# dual_motor_driver_v7.net
KiCad netlist of a schematic drawn in EAGLE
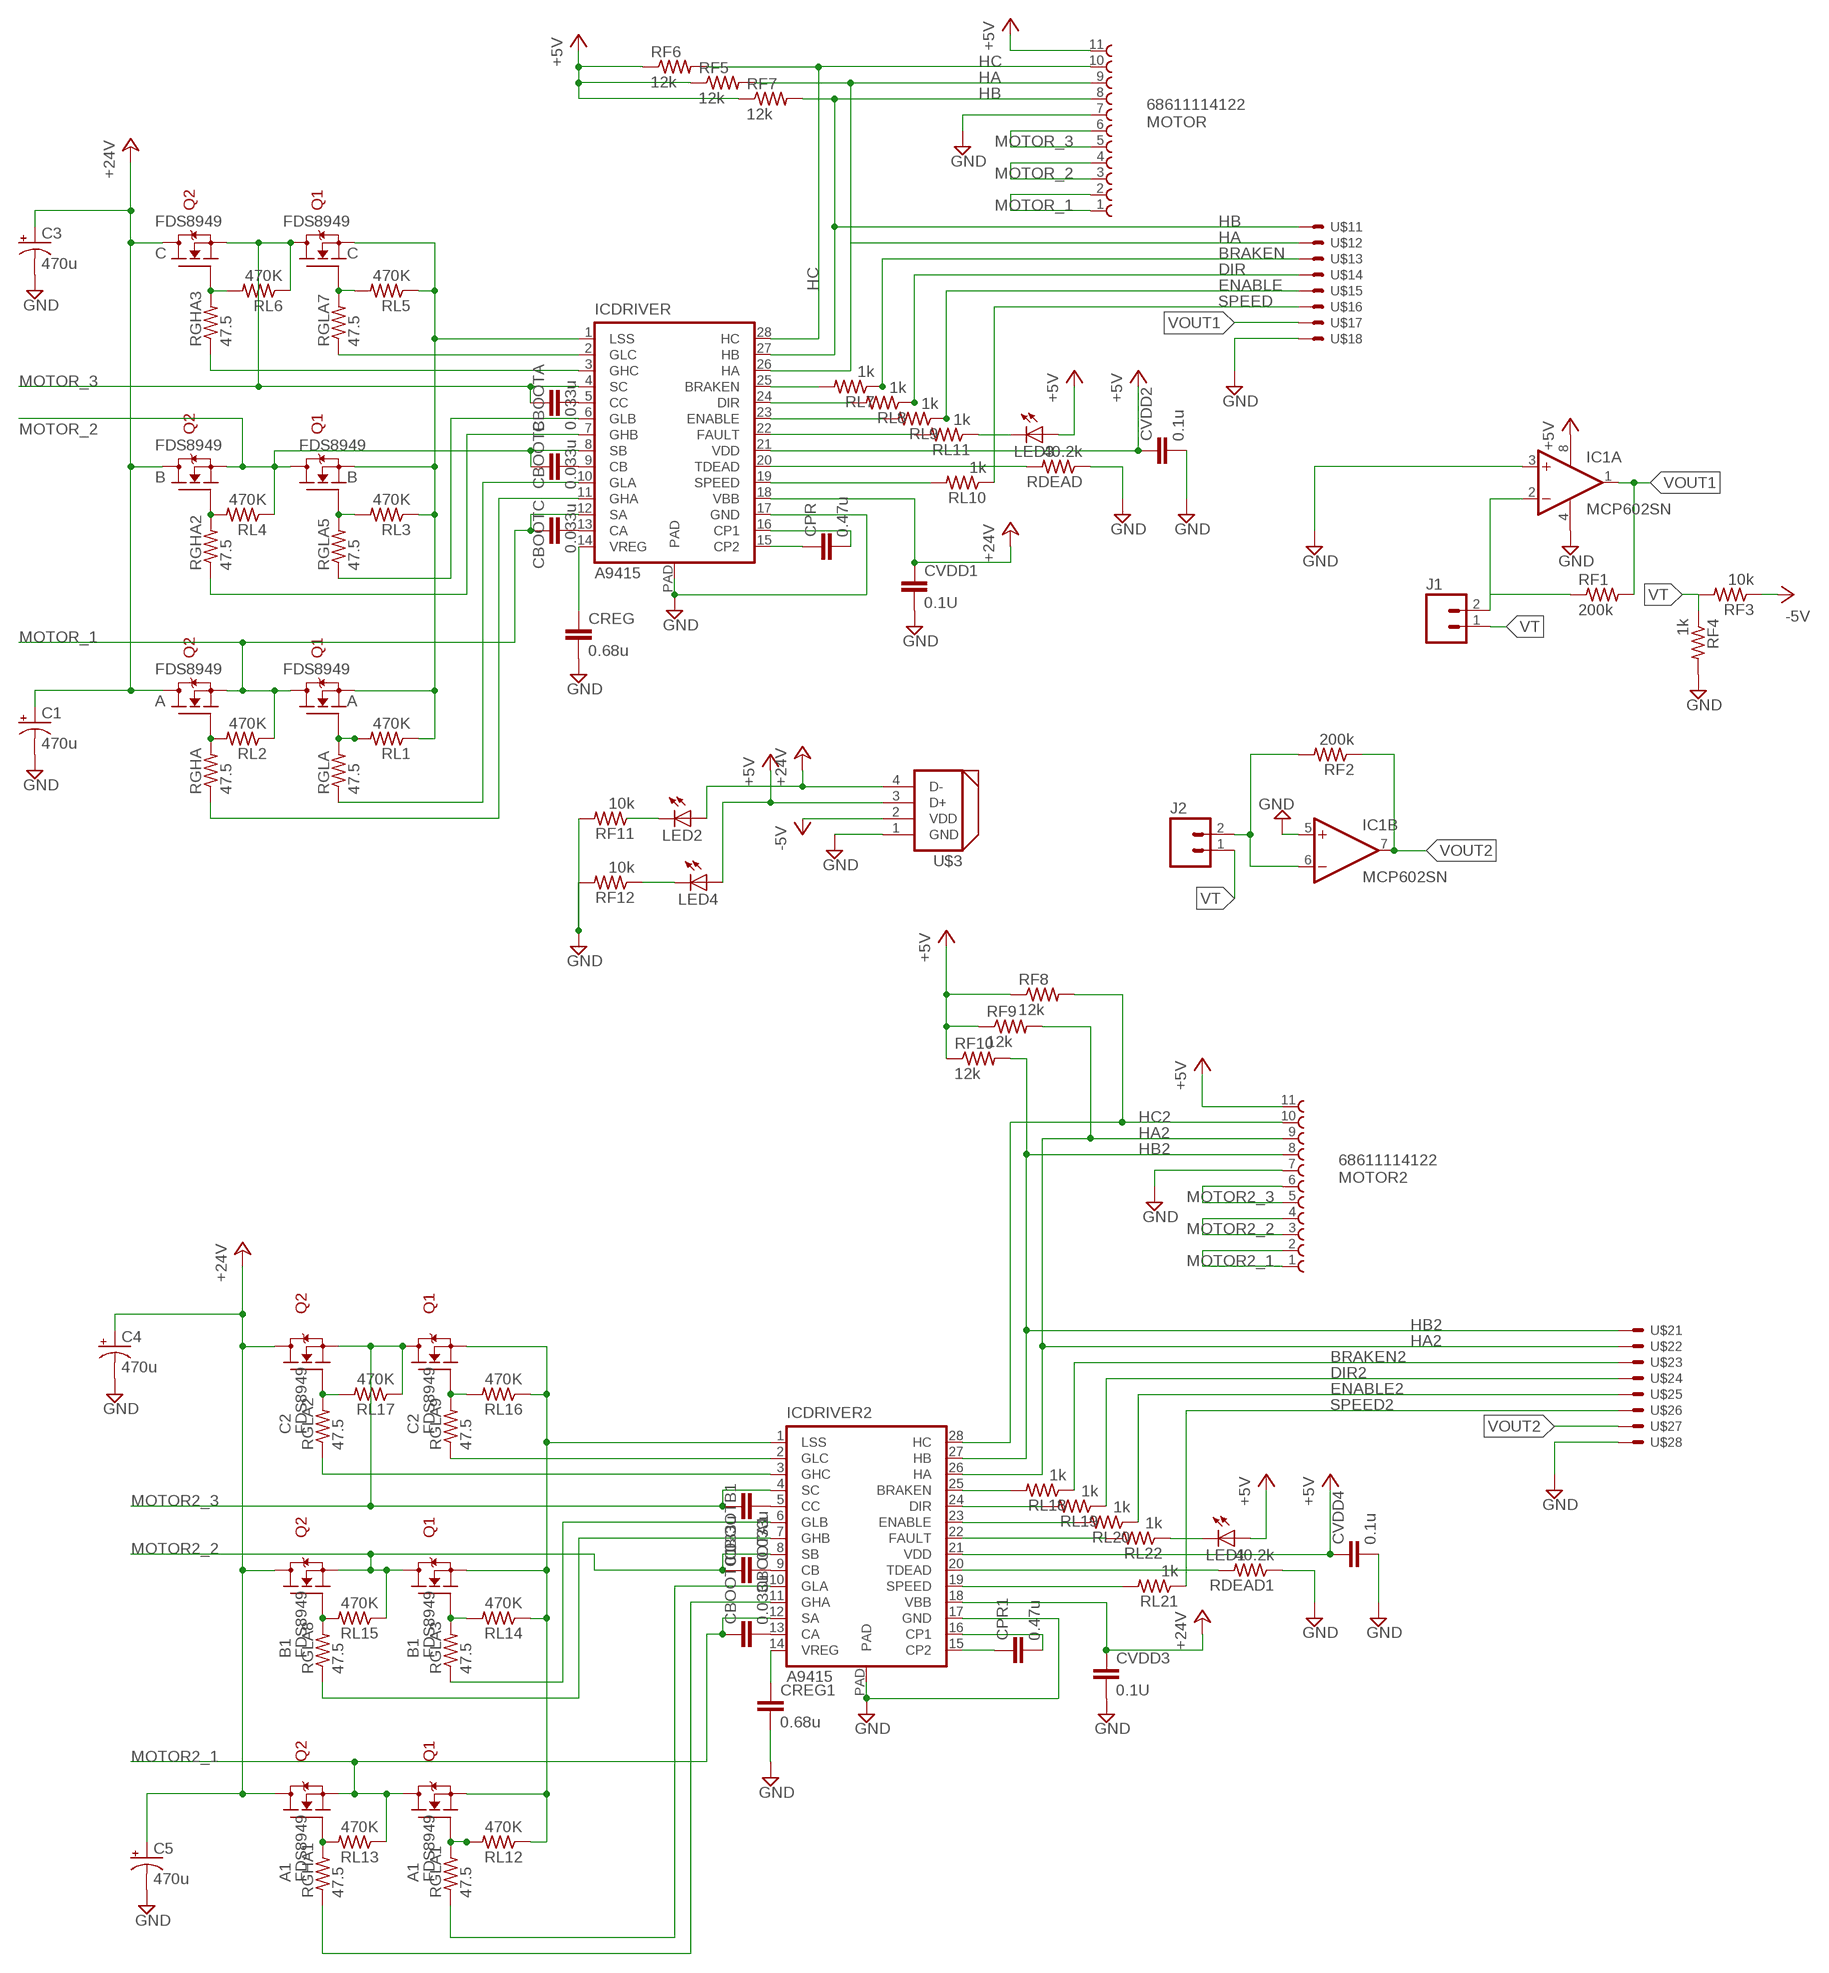
[diagram p0: schematic, sheet 1]

(export (version "E")
  (design (tool "Eeschema 10.0.6"))
  (components
    (comp (ref "A")
      (value "FDS8949")
      (footprint "eagle-import:SOIC8")
      (libsource (lib "eagle-import") (part "FDS8949"))
    )
    (comp (ref "A1")
      (value "FDS8949")
      (footprint "eagle-import:SOIC8")
      (libsource (lib "eagle-import") (part "FDS8949"))
    )
    (comp (ref "B")
      (value "FDS8949")
      (footprint "eagle-import:SOIC8")
      (libsource (lib "eagle-import") (part "FDS8949"))
    )
    (comp (ref "B1")
      (value "FDS8949")
      (footprint "eagle-import:SOIC8")
      (libsource (lib "eagle-import") (part "FDS8949"))
    )
    (comp (ref "C")
      (value "FDS8949")
      (footprint "eagle-import:SOIC8")
      (libsource (lib "eagle-import") (part "FDS8949"))
    )
    (comp (ref "C1")
      (value "470u")
      (footprint "eagle-import:140CLH-1010")
      (libsource (lib "eagle-import") (part "CPOL-US140CLH-1010"))
    )
    (comp (ref "C2")
      (value "FDS8949")
      (footprint "eagle-import:SOIC8")
      (libsource (lib "eagle-import") (part "FDS8949"))
    )
    (comp (ref "C3")
      (value "470u")
      (footprint "eagle-import:140CLH-1010")
      (libsource (lib "eagle-import") (part "CPOL-US140CLH-1010"))
    )
    (comp (ref "C4")
      (value "470u")
      (footprint "eagle-import:140CLH-1010")
      (libsource (lib "eagle-import") (part "CPOL-US140CLH-1010"))
    )
    (comp (ref "C5")
      (value "470u")
      (footprint "eagle-import:140CLH-1010")
      (libsource (lib "eagle-import") (part "CPOL-US140CLH-1010"))
    )
    (comp (ref "CBOOTA")
      (value "0.033u")
      (footprint "eagle-import:C0805")
      (libsource (lib "eagle-import") (part "C-EUC0805"))
    )
    (comp (ref "CBOOTA1")
      (value "0.033u")
      (footprint "eagle-import:C0805")
      (libsource (lib "eagle-import") (part "C-EUC0805"))
    )
    (comp (ref "CBOOTB")
      (value "0.033u")
      (footprint "eagle-import:C0805")
      (libsource (lib "eagle-import") (part "C-EUC0805"))
    )
    (comp (ref "CBOOTB1")
      (value "0.033u")
      (footprint "eagle-import:C0805")
      (libsource (lib "eagle-import") (part "C-EUC0805"))
    )
    (comp (ref "CBOOTC")
      (value "0.033u")
      (footprint "eagle-import:C0805")
      (libsource (lib "eagle-import") (part "C-EUC0805"))
    )
    (comp (ref "CBOOTC1")
      (value "0.033u")
      (footprint "eagle-import:C0805")
      (libsource (lib "eagle-import") (part "C-EUC0805"))
    )
    (comp (ref "CPR")
      (value "0.47u")
      (footprint "eagle-import:C0805")
      (libsource (lib "eagle-import") (part "C-EUC0805"))
    )
    (comp (ref "CPR1")
      (value "0.47u")
      (footprint "eagle-import:C0805")
      (libsource (lib "eagle-import") (part "C-EUC0805"))
    )
    (comp (ref "CREG")
      (value "0.68u")
      (footprint "eagle-import:C0805")
      (libsource (lib "eagle-import") (part "C-EUC0805"))
    )
    (comp (ref "CREG1")
      (value "0.68u")
      (footprint "eagle-import:C0805")
      (libsource (lib "eagle-import") (part "C-EUC0805"))
    )
    (comp (ref "CVDD1")
      (value "0.1U")
      (footprint "eagle-import:C0805")
      (libsource (lib "eagle-import") (part "C-EUC0805"))
    )
    (comp (ref "CVDD2")
      (value "0.1u")
      (footprint "eagle-import:C0805")
      (libsource (lib "eagle-import") (part "C-EUC0805"))
    )
    (comp (ref "CVDD3")
      (value "0.1U")
      (footprint "eagle-import:C0805")
      (libsource (lib "eagle-import") (part "C-EUC0805"))
    )
    (comp (ref "CVDD4")
      (value "0.1u")
      (footprint "eagle-import:C0805")
      (libsource (lib "eagle-import") (part "C-EUC0805"))
    )
    (comp (ref "IC1")
      (value "MCP602SN")
      (footprint "eagle-import:SO08")
      (libsource (lib "eagle-import") (part "MCP602SN"))
    )
    (comp (ref "ICDRIVER")
      (value "A9415")
      (footprint "eagle-import:TSSOP28")
      (libsource (lib "eagle-import") (part "A9415"))
    )
    (comp (ref "ICDRIVER2")
      (value "A9415")
      (footprint "eagle-import:TSSOP28")
      (libsource (lib "eagle-import") (part "A9415"))
    )
    (comp (ref "J1")
      (value "M02PTH")
      (footprint "eagle-import:1X02")
      (libsource (lib "eagle-import") (part "M02PTH"))
    )
    (comp (ref "J2")
      (value "M02PTH")
      (footprint "eagle-import:1X02")
      (libsource (lib "eagle-import") (part "M02PTH"))
    )
    (comp (ref "LED1")
      (value "LEDCHIPLED_0805")
      (footprint "eagle-import:CHIPLED_0805")
      (libsource (lib "eagle-import") (part "LEDCHIPLED_0805"))
    )
    (comp (ref "LED2")
      (value "LEDCHIPLED_0805")
      (footprint "eagle-import:CHIPLED_0805")
      (libsource (lib "eagle-import") (part "LEDCHIPLED_0805"))
    )
    (comp (ref "LED3")
      (value "LEDCHIPLED_0805")
      (footprint "eagle-import:CHIPLED_0805")
      (libsource (lib "eagle-import") (part "LEDCHIPLED_0805"))
    )
    (comp (ref "LED4")
      (value "LEDCHIPLED_0805")
      (footprint "eagle-import:CHIPLED_0805")
      (libsource (lib "eagle-import") (part "LEDCHIPLED_0805"))
    )
    (comp (ref "MOTOR")
      (value "68611114122")
      (footprint "eagle-import:68611114122")
      (libsource (lib "eagle-import") (part "68611114122"))
    )
    (comp (ref "MOTOR2")
      (value "68611114122")
      (footprint "eagle-import:68611114122")
      (libsource (lib "eagle-import") (part "68611114122"))
    )
    (comp (ref "RDEAD")
      (value "40.2k")
      (footprint "eagle-import:R0805")
      (libsource (lib "eagle-import") (part "R-US_R0805"))
    )
    (comp (ref "RDEAD1")
      (value "40.2k")
      (footprint "eagle-import:R0805")
      (libsource (lib "eagle-import") (part "R-US_R0805"))
    )
    (comp (ref "RF1")
      (value "200k")
      (footprint "eagle-import:R0805")
      (libsource (lib "eagle-import") (part "R-US_R0805"))
    )
    (comp (ref "RF2")
      (value "200k")
      (footprint "eagle-import:R0805")
      (libsource (lib "eagle-import") (part "R-US_R0805"))
    )
    (comp (ref "RF3")
      (value "10k")
      (footprint "eagle-import:R0805")
      (libsource (lib "eagle-import") (part "R-US_R0805"))
    )
    (comp (ref "RF4")
      (value "1k")
      (footprint "eagle-import:R0805")
      (libsource (lib "eagle-import") (part "R-US_R0805"))
    )
    (comp (ref "RF5")
      (value "12k")
      (footprint "eagle-import:R0805")
      (libsource (lib "eagle-import") (part "R-US_R0805"))
    )
    (comp (ref "RF6")
      (value "12k")
      (footprint "eagle-import:R0805")
      (libsource (lib "eagle-import") (part "R-US_R0805"))
    )
    (comp (ref "RF7")
      (value "12k")
      (footprint "eagle-import:R0805")
      (libsource (lib "eagle-import") (part "R-US_R0805"))
    )
    (comp (ref "RF8")
      (value "12k")
      (footprint "eagle-import:R0805")
      (libsource (lib "eagle-import") (part "R-US_R0805"))
    )
    (comp (ref "RF9")
      (value "12k")
      (footprint "eagle-import:R0805")
      (libsource (lib "eagle-import") (part "R-US_R0805"))
    )
    (comp (ref "RF10")
      (value "12k")
      (footprint "eagle-import:R0805")
      (libsource (lib "eagle-import") (part "R-US_R0805"))
    )
    (comp (ref "RF11")
      (value "10k")
      (footprint "eagle-import:R0805")
      (libsource (lib "eagle-import") (part "R-US_R0805"))
    )
    (comp (ref "RF12")
      (value "10k")
      (footprint "eagle-import:R0805")
      (libsource (lib "eagle-import") (part "R-US_R0805"))
    )
    (comp (ref "RGHA")
      (value "47.5")
      (footprint "eagle-import:R0805")
      (libsource (lib "eagle-import") (part "R-US_R0805"))
    )
    (comp (ref "RGHA1")
      (value "47.5")
      (footprint "eagle-import:R0805")
      (libsource (lib "eagle-import") (part "R-US_R0805"))
    )
    (comp (ref "RGHA2")
      (value "47.5")
      (footprint "eagle-import:R0805")
      (libsource (lib "eagle-import") (part "R-US_R0805"))
    )
    (comp (ref "RGHA3")
      (value "47.5")
      (footprint "eagle-import:R0805")
      (libsource (lib "eagle-import") (part "R-US_R0805"))
    )
    (comp (ref "RGLA")
      (value "47.5")
      (footprint "eagle-import:R0805")
      (libsource (lib "eagle-import") (part "R-US_R0805"))
    )
    (comp (ref "RGLA1")
      (value "47.5")
      (footprint "eagle-import:R0805")
      (libsource (lib "eagle-import") (part "R-US_R0805"))
    )
    (comp (ref "RGLA2")
      (value "47.5")
      (footprint "eagle-import:R0805")
      (libsource (lib "eagle-import") (part "R-US_R0805"))
    )
    (comp (ref "RGLA3")
      (value "47.5")
      (footprint "eagle-import:R0805")
      (libsource (lib "eagle-import") (part "R-US_R0805"))
    )
    (comp (ref "RGLA5")
      (value "47.5")
      (footprint "eagle-import:R0805")
      (libsource (lib "eagle-import") (part "R-US_R0805"))
    )
    (comp (ref "RGLA7")
      (value "47.5")
      (footprint "eagle-import:R0805")
      (libsource (lib "eagle-import") (part "R-US_R0805"))
    )
    (comp (ref "RGLA8")
      (value "47.5")
      (footprint "eagle-import:R0805")
      (libsource (lib "eagle-import") (part "R-US_R0805"))
    )
    (comp (ref "RGLA9")
      (value "47.5")
      (footprint "eagle-import:R0805")
      (libsource (lib "eagle-import") (part "R-US_R0805"))
    )
    (comp (ref "RL1")
      (value "470K")
      (footprint "eagle-import:R0805")
      (libsource (lib "eagle-import") (part "R-US_R0805"))
    )
    (comp (ref "RL2")
      (value "470K")
      (footprint "eagle-import:R0805")
      (libsource (lib "eagle-import") (part "R-US_R0805"))
    )
    (comp (ref "RL3")
      (value "470K")
      (footprint "eagle-import:R0805")
      (libsource (lib "eagle-import") (part "R-US_R0805"))
    )
    (comp (ref "RL4")
      (value "470K")
      (footprint "eagle-import:R0805")
      (libsource (lib "eagle-import") (part "R-US_R0805"))
    )
    (comp (ref "RL5")
      (value "470K")
      (footprint "eagle-import:R0805")
      (libsource (lib "eagle-import") (part "R-US_R0805"))
    )
    (comp (ref "RL6")
      (value "470K")
      (footprint "eagle-import:R0805")
      (libsource (lib "eagle-import") (part "R-US_R0805"))
    )
    (comp (ref "RL7")
      (value "1k")
      (footprint "eagle-import:R0805")
      (libsource (lib "eagle-import") (part "R-US_R0805"))
    )
    (comp (ref "RL8")
      (value "1k")
      (footprint "eagle-import:R0805")
      (libsource (lib "eagle-import") (part "R-US_R0805"))
    )
    (comp (ref "RL9")
      (value "1k")
      (footprint "eagle-import:R0805")
      (libsource (lib "eagle-import") (part "R-US_R0805"))
    )
    (comp (ref "RL10")
      (value "1k")
      (footprint "eagle-import:R0805")
      (libsource (lib "eagle-import") (part "R-US_R0805"))
    )
    (comp (ref "RL11")
      (value "1k")
      (footprint "eagle-import:R0805")
      (libsource (lib "eagle-import") (part "R-US_R0805"))
    )
    (comp (ref "RL12")
      (value "470K")
      (footprint "eagle-import:R0805")
      (libsource (lib "eagle-import") (part "R-US_R0805"))
    )
    (comp (ref "RL13")
      (value "470K")
      (footprint "eagle-import:R0805")
      (libsource (lib "eagle-import") (part "R-US_R0805"))
    )
    (comp (ref "RL14")
      (value "470K")
      (footprint "eagle-import:R0805")
      (libsource (lib "eagle-import") (part "R-US_R0805"))
    )
    (comp (ref "RL15")
      (value "470K")
      (footprint "eagle-import:R0805")
      (libsource (lib "eagle-import") (part "R-US_R0805"))
    )
    (comp (ref "RL16")
      (value "470K")
      (footprint "eagle-import:R0805")
      (libsource (lib "eagle-import") (part "R-US_R0805"))
    )
    (comp (ref "RL17")
      (value "470K")
      (footprint "eagle-import:R0805")
      (libsource (lib "eagle-import") (part "R-US_R0805"))
    )
    (comp (ref "RL18")
      (value "1k")
      (footprint "eagle-import:R0805")
      (libsource (lib "eagle-import") (part "R-US_R0805"))
    )
    (comp (ref "RL19")
      (value "1k")
      (footprint "eagle-import:R0805")
      (libsource (lib "eagle-import") (part "R-US_R0805"))
    )
    (comp (ref "RL20")
      (value "1k")
      (footprint "eagle-import:R0805")
      (libsource (lib "eagle-import") (part "R-US_R0805"))
    )
    (comp (ref "RL21")
      (value "1k")
      (footprint "eagle-import:R0805")
      (libsource (lib "eagle-import") (part "R-US_R0805"))
    )
    (comp (ref "RL22")
      (value "1k")
      (footprint "eagle-import:R0805")
      (libsource (lib "eagle-import") (part "R-US_R0805"))
    )
    (comp (ref "U$1")
      (value "JST8")
      (footprint "eagle-import:JST")
      (libsource (lib "eagle-import") (part "JST8"))
    )
    (comp (ref "U$2")
      (value "JST8")
      (footprint "eagle-import:JST")
      (libsource (lib "eagle-import") (part "JST8"))
    )
    (comp (ref "U$3")
      (value "DYNAMIXEL_RS485")
      (footprint "eagle-import:DYNAMIXEL_SPOX_04")
      (libsource (lib "eagle-import") (part "DYNAMIXEL_RS485"))
    )
  )
  (nets
    (net (code "1") (name "+5V") (class "Default")
      (node (ref "CVDD2") (pin "1") (pinfunction "1_1") (pintype "passive"))
      (node (ref "CVDD4") (pin "1") (pinfunction "1_1") (pintype "passive"))
      (node (ref "IC1") (pin "8") (pinfunction "V+_8") (pintype "power_in"))
      (node (ref "ICDRIVER") (pin "21") (pinfunction "VDD_21") (pintype "power_in"))
      (node (ref "ICDRIVER2") (pin "21") (pinfunction "VDD_21") (pintype "power_in"))
      (node (ref "LED1") (pin "A") (pinfunction "A_A") (pintype "passive"))
      (node (ref "LED3") (pin "A") (pinfunction "A_A") (pintype "passive"))
      (node (ref "LED4") (pin "A") (pinfunction "A_A") (pintype "passive"))
      (node (ref "MOTOR") (pin "11") (pinfunction "11_11") (pintype "passive"))
      (node (ref "MOTOR2") (pin "11") (pinfunction "11_11") (pintype "passive"))
      (node (ref "RF10") (pin "1") (pinfunction "1_1") (pintype "passive"))
      (node (ref "RF5") (pin "1") (pinfunction "1_1") (pintype "passive"))
      (node (ref "RF6") (pin "1") (pinfunction "1_1") (pintype "passive"))
      (node (ref "RF7") (pin "1") (pinfunction "1_1") (pintype "passive"))
      (node (ref "RF8") (pin "1") (pinfunction "1_1") (pintype "passive"))
      (node (ref "RF9") (pin "1") (pinfunction "1_1") (pintype "passive"))
      (node (ref "U$3") (pin "3") (pinfunction "D+_3") (pintype "bidirectional"))
    )
    (net (code "2") (name "+24V") (class "Default")
      (node (ref "A") (pin "5") (pinfunction "D2_5") (pintype "passive"))
      (node (ref "A") (pin "6") (pinfunction "D2_6") (pintype "passive"))
      (node (ref "A1") (pin "5") (pinfunction "D2_5") (pintype "passive"))
      (node (ref "A1") (pin "6") (pinfunction "D2_6") (pintype "passive"))
      (node (ref "B") (pin "5") (pinfunction "D2_5") (pintype "passive"))
      (node (ref "B") (pin "6") (pinfunction "D2_6") (pintype "passive"))
      (node (ref "B1") (pin "5") (pinfunction "D2_5") (pintype "passive"))
      (node (ref "B1") (pin "6") (pinfunction "D2_6") (pintype "passive"))
      (node (ref "C") (pin "5") (pinfunction "D2_5") (pintype "passive"))
      (node (ref "C") (pin "6") (pinfunction "D2_6") (pintype "passive"))
      (node (ref "C1") (pin "+") (pinfunction "+_+") (pintype "passive"))
      (node (ref "C2") (pin "5") (pinfunction "D2_5") (pintype "passive"))
      (node (ref "C2") (pin "6") (pinfunction "D2_6") (pintype "passive"))
      (node (ref "C3") (pin "+") (pinfunction "+_+") (pintype "passive"))
      (node (ref "C4") (pin "+") (pinfunction "+_+") (pintype "passive"))
      (node (ref "C5") (pin "+") (pinfunction "+_+") (pintype "passive"))
      (node (ref "CVDD1") (pin "1") (pinfunction "1_1") (pintype "passive"))
      (node (ref "CVDD3") (pin "1") (pinfunction "1_1") (pintype "passive"))
      (node (ref "ICDRIVER") (pin "18") (pinfunction "VBB_18") (pintype "power_in"))
      (node (ref "ICDRIVER2") (pin "18") (pinfunction "VBB_18") (pintype "power_in"))
      (node (ref "LED2") (pin "A") (pinfunction "A_A") (pintype "passive"))
      (node (ref "U$3") (pin "4") (pinfunction "D-_4") (pintype "bidirectional"))
    )
    (net (code "3") (name "-5V") (class "Default")
      (node (ref "RF3") (pin "1") (pinfunction "1_1") (pintype "passive"))
      (node (ref "U$3") (pin "2") (pinfunction "VDD_2") (pintype "power_in"))
    )
    (net (code "4") (name "/BRAKEN") (class "Default")
      (node (ref "RL7") (pin "1") (pinfunction "1_1") (pintype "passive"))
      (node (ref "U$1") (pin "3") (pinfunction "S_3") (pintype "passive"))
    )
    (net (code "5") (name "/BRAKEN2") (class "Default")
      (node (ref "RL18") (pin "1") (pinfunction "1_1") (pintype "passive"))
      (node (ref "U$2") (pin "3") (pinfunction "S_3") (pintype "passive"))
    )
    (net (code "6") (name "/DIR") (class "Default")
      (node (ref "RL8") (pin "1") (pinfunction "1_1") (pintype "passive"))
      (node (ref "U$1") (pin "4") (pinfunction "S_4") (pintype "passive"))
    )
    (net (code "7") (name "/DIR2") (class "Default")
      (node (ref "RL19") (pin "1") (pinfunction "1_1") (pintype "passive"))
      (node (ref "U$2") (pin "4") (pinfunction "S_4") (pintype "passive"))
    )
    (net (code "8") (name "/ENABLE") (class "Default")
      (node (ref "RL9") (pin "1") (pinfunction "1_1") (pintype "passive"))
      (node (ref "U$1") (pin "5") (pinfunction "S_5") (pintype "passive"))
    )
    (net (code "9") (name "/ENABLE2") (class "Default")
      (node (ref "RL20") (pin "1") (pinfunction "1_1") (pintype "passive"))
      (node (ref "U$2") (pin "5") (pinfunction "S_5") (pintype "passive"))
    )
    (net (code "10") (name "/HA") (class "Default")
      (node (ref "ICDRIVER") (pin "26") (pinfunction "HA_26") (pintype "input"))
      (node (ref "MOTOR") (pin "9") (pinfunction "9_9") (pintype "passive"))
      (node (ref "RF5") (pin "2") (pinfunction "2_2") (pintype "passive"))
      (node (ref "U$1") (pin "2") (pinfunction "S_2") (pintype "passive"))
    )
    (net (code "11") (name "/HA2") (class "Default")
      (node (ref "ICDRIVER2") (pin "26") (pinfunction "HA_26") (pintype "input"))
      (node (ref "MOTOR2") (pin "9") (pinfunction "9_9") (pintype "passive"))
      (node (ref "RF9") (pin "2") (pinfunction "2_2") (pintype "passive"))
      (node (ref "U$2") (pin "2") (pinfunction "S_2") (pintype "passive"))
    )
    (net (code "12") (name "/HB") (class "Default")
      (node (ref "ICDRIVER") (pin "27") (pinfunction "HB_27") (pintype "input"))
      (node (ref "MOTOR") (pin "8") (pinfunction "8_8") (pintype "passive"))
      (node (ref "RF7") (pin "2") (pinfunction "2_2") (pintype "passive"))
      (node (ref "U$1") (pin "1") (pinfunction "S_1") (pintype "passive"))
    )
    (net (code "13") (name "/HB2") (class "Default")
      (node (ref "ICDRIVER2") (pin "27") (pinfunction "HB_27") (pintype "input"))
      (node (ref "MOTOR2") (pin "8") (pinfunction "8_8") (pintype "passive"))
      (node (ref "RF10") (pin "2") (pinfunction "2_2") (pintype "passive"))
      (node (ref "U$2") (pin "1") (pinfunction "S_1") (pintype "passive"))
    )
    (net (code "14") (name "/HC") (class "Default")
      (node (ref "ICDRIVER") (pin "28") (pinfunction "HC_28") (pintype "input"))
      (node (ref "MOTOR") (pin "10") (pinfunction "10_10") (pintype "passive"))
      (node (ref "RF6") (pin "2") (pinfunction "2_2") (pintype "passive"))
    )
    (net (code "15") (name "/HC2") (class "Default")
      (node (ref "ICDRIVER2") (pin "28") (pinfunction "HC_28") (pintype "input"))
      (node (ref "MOTOR2") (pin "10") (pinfunction "10_10") (pintype "passive"))
      (node (ref "RF8") (pin "2") (pinfunction "2_2") (pintype "passive"))
    )
    (net (code "16") (name "/MOTOR2_1") (class "Default")
      (node (ref "A1") (pin "3") (pinfunction "S2_3") (pintype "passive"))
      (node (ref "A1") (pin "7") (pinfunction "D1_7") (pintype "passive"))
      (node (ref "A1") (pin "8") (pinfunction "D1_8") (pintype "passive"))
      (node (ref "CBOOTC1") (pin "1") (pinfunction "1_1") (pintype "passive"))
      (node (ref "ICDRIVER2") (pin "12") (pinfunction "SA_12") (pintype "output"))
      (node (ref "MOTOR2") (pin "1") (pinfunction "1_1") (pintype "passive"))
      (node (ref "MOTOR2") (pin "2") (pinfunction "2_2") (pintype "passive"))
      (node (ref "RL13") (pin "1") (pinfunction "1_1") (pintype "passive"))
    )
    (net (code "17") (name "/MOTOR2_2") (class "Default")
      (node (ref "B1") (pin "3") (pinfunction "S2_3") (pintype "passive"))
      (node (ref "B1") (pin "7") (pinfunction "D1_7") (pintype "passive"))
      (node (ref "B1") (pin "8") (pinfunction "D1_8") (pintype "passive"))
      (node (ref "CBOOTB1") (pin "1") (pinfunction "1_1") (pintype "passive"))
      (node (ref "ICDRIVER2") (pin "8") (pinfunction "SB_8") (pintype "output"))
      (node (ref "MOTOR2") (pin "3") (pinfunction "3_3") (pintype "passive"))
      (node (ref "MOTOR2") (pin "4") (pinfunction "4_4") (pintype "passive"))
      (node (ref "RL15") (pin "1") (pinfunction "1_1") (pintype "passive"))
    )
    (net (code "18") (name "/MOTOR2_3") (class "Default")
      (node (ref "C2") (pin "3") (pinfunction "S2_3") (pintype "passive"))
      (node (ref "C2") (pin "7") (pinfunction "D1_7") (pintype "passive"))
      (node (ref "C2") (pin "8") (pinfunction "D1_8") (pintype "passive"))
      (node (ref "CBOOTA1") (pin "2") (pinfunction "2_2") (pintype "passive"))
      (node (ref "ICDRIVER2") (pin "4") (pinfunction "SC_4") (pintype "output"))
      (node (ref "MOTOR2") (pin "5") (pinfunction "5_5") (pintype "passive"))
      (node (ref "MOTOR2") (pin "6") (pinfunction "6_6") (pintype "passive"))
      (node (ref "RL17") (pin "1") (pinfunction "1_1") (pintype "passive"))
    )
    (net (code "19") (name "/MOTOR_1") (class "Default")
      (node (ref "A") (pin "3") (pinfunction "S2_3") (pintype "passive"))
      (node (ref "A") (pin "7") (pinfunction "D1_7") (pintype "passive"))
      (node (ref "A") (pin "8") (pinfunction "D1_8") (pintype "passive"))
      (node (ref "CBOOTC") (pin "1") (pinfunction "1_1") (pintype "passive"))
      (node (ref "ICDRIVER") (pin "12") (pinfunction "SA_12") (pintype "output"))
      (node (ref "MOTOR") (pin "1") (pinfunction "1_1") (pintype "passive"))
      (node (ref "MOTOR") (pin "2") (pinfunction "2_2") (pintype "passive"))
      (node (ref "RL2") (pin "1") (pinfunction "1_1") (pintype "passive"))
    )
    (net (code "20") (name "/MOTOR_2") (class "Default")
      (node (ref "B") (pin "3") (pinfunction "S2_3") (pintype "passive"))
      (node (ref "B") (pin "7") (pinfunction "D1_7") (pintype "passive"))
      (node (ref "B") (pin "8") (pinfunction "D1_8") (pintype "passive"))
      (node (ref "CBOOTB") (pin "1") (pinfunction "1_1") (pintype "passive"))
      (node (ref "ICDRIVER") (pin "8") (pinfunction "SB_8") (pintype "output"))
      (node (ref "MOTOR") (pin "3") (pinfunction "3_3") (pintype "passive"))
      (node (ref "MOTOR") (pin "4") (pinfunction "4_4") (pintype "passive"))
      (node (ref "RL4") (pin "1") (pinfunction "1_1") (pintype "passive"))
    )
    (net (code "21") (name "/MOTOR_3") (class "Default")
      (node (ref "C") (pin "3") (pinfunction "S2_3") (pintype "passive"))
      (node (ref "C") (pin "7") (pinfunction "D1_7") (pintype "passive"))
      (node (ref "C") (pin "8") (pinfunction "D1_8") (pintype "passive"))
      (node (ref "CBOOTA") (pin "2") (pinfunction "2_2") (pintype "passive"))
      (node (ref "ICDRIVER") (pin "4") (pinfunction "SC_4") (pintype "output"))
      (node (ref "MOTOR") (pin "5") (pinfunction "5_5") (pintype "passive"))
      (node (ref "MOTOR") (pin "6") (pinfunction "6_6") (pintype "passive"))
      (node (ref "RL6") (pin "1") (pinfunction "1_1") (pintype "passive"))
    )
    (net (code "22") (name "/SPEED") (class "Default")
      (node (ref "RL10") (pin "1") (pinfunction "1_1") (pintype "passive"))
      (node (ref "U$1") (pin "6") (pinfunction "S_6") (pintype "passive"))
    )
    (net (code "23") (name "/SPEED2") (class "Default")
      (node (ref "RL21") (pin "1") (pinfunction "1_1") (pintype "passive"))
      (node (ref "U$2") (pin "6") (pinfunction "S_6") (pintype "passive"))
    )
    (net (code "24") (name "GND") (class "Default")
      (node (ref "A") (pin "1") (pinfunction "S1_1") (pintype "passive"))
      (node (ref "A1") (pin "1") (pinfunction "S1_1") (pintype "passive"))
      (node (ref "B") (pin "1") (pinfunction "S1_1") (pintype "passive"))
      (node (ref "B1") (pin "1") (pinfunction "S1_1") (pintype "passive"))
      (node (ref "C") (pin "1") (pinfunction "S1_1") (pintype "passive"))
      (node (ref "C1") (pin "-") (pinfunction "-_-") (pintype "passive"))
      (node (ref "C2") (pin "1") (pinfunction "S1_1") (pintype "passive"))
      (node (ref "C3") (pin "-") (pinfunction "-_-") (pintype "passive"))
      (node (ref "C4") (pin "-") (pinfunction "-_-") (pintype "passive"))
      (node (ref "C5") (pin "-") (pinfunction "-_-") (pintype "passive"))
      (node (ref "CREG") (pin "2") (pinfunction "2_2") (pintype "passive"))
      (node (ref "CREG1") (pin "2") (pinfunction "2_2") (pintype "passive"))
      (node (ref "CVDD1") (pin "2") (pinfunction "2_2") (pintype "passive"))
      (node (ref "CVDD2") (pin "2") (pinfunction "2_2") (pintype "passive"))
      (node (ref "CVDD3") (pin "2") (pinfunction "2_2") (pintype "passive"))
      (node (ref "CVDD4") (pin "2") (pinfunction "2_2") (pintype "passive"))
      (node (ref "IC1") (pin "3") (pinfunction "+IN_3") (pintype "input"))
      (node (ref "IC1") (pin "4") (pinfunction "V-_4") (pintype "power_in"))
      (node (ref "IC1") (pin "5") (pinfunction "+IN_5") (pintype "input"))
      (node (ref "ICDRIVER") (pin "1") (pinfunction "LSS_1") (pintype "input"))
      (node (ref "ICDRIVER") (pin "17") (pinfunction "GND_17") (pintype "power_in"))
      (node (ref "ICDRIVER") (pin "PAD") (pinfunction "PAD_PAD") (pintype "power_in"))
      (node (ref "ICDRIVER2") (pin "1") (pinfunction "LSS_1") (pintype "input"))
      (node (ref "ICDRIVER2") (pin "17") (pinfunction "GND_17") (pintype "power_in"))
      (node (ref "ICDRIVER2") (pin "PAD") (pinfunction "PAD_PAD") (pintype "power_in"))
      (node (ref "MOTOR") (pin "7") (pinfunction "7_7") (pintype "passive"))
      (node (ref "MOTOR2") (pin "7") (pinfunction "7_7") (pintype "passive"))
      (node (ref "RDEAD") (pin "1") (pinfunction "1_1") (pintype "passive"))
      (node (ref "RDEAD1") (pin "1") (pinfunction "1_1") (pintype "passive"))
      (node (ref "RF11") (pin "2") (pinfunction "2_2") (pintype "passive"))
      (node (ref "RF12") (pin "2") (pinfunction "2_2") (pintype "passive"))
      (node (ref "RF4") (pin "2") (pinfunction "2_2") (pintype "passive"))
      (node (ref "RL1") (pin "1") (pinfunction "1_1") (pintype "passive"))
      (node (ref "RL12") (pin "1") (pinfunction "1_1") (pintype "passive"))
      (node (ref "RL14") (pin "1") (pinfunction "1_1") (pintype "passive"))
      (node (ref "RL16") (pin "1") (pinfunction "1_1") (pintype "passive"))
      (node (ref "RL3") (pin "1") (pinfunction "1_1") (pintype "passive"))
      (node (ref "RL5") (pin "1") (pinfunction "1_1") (pintype "passive"))
      (node (ref "U$1") (pin "8") (pinfunction "S_8") (pintype "passive"))
      (node (ref "U$2") (pin "8") (pinfunction "S_8") (pintype "passive"))
      (node (ref "U$3") (pin "1") (pinfunction "GND_1") (pintype "power_in"))
    )
    (net (code "25") (name "Net-(A-G1)") (class "Default")
      (node (ref "A") (pin "2") (pinfunction "G1_2") (pintype "passive"))
      (node (ref "RGLA") (pin "2") (pinfunction "2_2") (pintype "passive"))
      (node (ref "RL1") (pin "2") (pinfunction "2_2") (pintype "passive"))
    )
    (net (code "26") (name "Net-(A-G2)") (class "Default")
      (node (ref "A") (pin "4") (pinfunction "G2_4") (pintype "passive"))
      (node (ref "RGHA") (pin "2") (pinfunction "2_2") (pintype "passive"))
      (node (ref "RL2") (pin "2") (pinfunction "2_2") (pintype "passive"))
    )
    (net (code "27") (name "Net-(A1-G1)") (class "Default")
      (node (ref "A1") (pin "2") (pinfunction "G1_2") (pintype "passive"))
      (node (ref "RGLA1") (pin "2") (pinfunction "2_2") (pintype "passive"))
      (node (ref "RL12") (pin "2") (pinfunction "2_2") (pintype "passive"))
    )
    (net (code "28") (name "Net-(A1-G2)") (class "Default")
      (node (ref "A1") (pin "4") (pinfunction "G2_4") (pintype "passive"))
      (node (ref "RGHA1") (pin "2") (pinfunction "2_2") (pintype "passive"))
      (node (ref "RL13") (pin "2") (pinfunction "2_2") (pintype "passive"))
    )
    (net (code "29") (name "Net-(B-G1)") (class "Default")
      (node (ref "B") (pin "2") (pinfunction "G1_2") (pintype "passive"))
      (node (ref "RGLA5") (pin "2") (pinfunction "2_2") (pintype "passive"))
      (node (ref "RL3") (pin "2") (pinfunction "2_2") (pintype "passive"))
    )
    (net (code "30") (name "Net-(B-G2)") (class "Default")
      (node (ref "B") (pin "4") (pinfunction "G2_4") (pintype "passive"))
      (node (ref "RGHA2") (pin "2") (pinfunction "2_2") (pintype "passive"))
      (node (ref "RL4") (pin "2") (pinfunction "2_2") (pintype "passive"))
    )
    (net (code "31") (name "Net-(B1-G1)") (class "Default")
      (node (ref "B1") (pin "2") (pinfunction "G1_2") (pintype "passive"))
      (node (ref "RGLA3") (pin "2") (pinfunction "2_2") (pintype "passive"))
      (node (ref "RL14") (pin "2") (pinfunction "2_2") (pintype "passive"))
    )
    (net (code "32") (name "Net-(B1-G2)") (class "Default")
      (node (ref "B1") (pin "4") (pinfunction "G2_4") (pintype "passive"))
      (node (ref "RGLA8") (pin "2") (pinfunction "2_2") (pintype "passive"))
      (node (ref "RL15") (pin "2") (pinfunction "2_2") (pintype "passive"))
    )
    (net (code "33") (name "Net-(C-G1)") (class "Default")
      (node (ref "C") (pin "2") (pinfunction "G1_2") (pintype "passive"))
      (node (ref "RGLA7") (pin "2") (pinfunction "2_2") (pintype "passive"))
      (node (ref "RL5") (pin "2") (pinfunction "2_2") (pintype "passive"))
    )
    (net (code "34") (name "Net-(C-G2)") (class "Default")
      (node (ref "C") (pin "4") (pinfunction "G2_4") (pintype "passive"))
      (node (ref "RGHA3") (pin "2") (pinfunction "2_2") (pintype "passive"))
      (node (ref "RL6") (pin "2") (pinfunction "2_2") (pintype "passive"))
    )
    (net (code "35") (name "Net-(C2-G1)") (class "Default")
      (node (ref "C2") (pin "2") (pinfunction "G1_2") (pintype "passive"))
      (node (ref "RGLA9") (pin "2") (pinfunction "2_2") (pintype "passive"))
      (node (ref "RL16") (pin "2") (pinfunction "2_2") (pintype "passive"))
    )
    (net (code "36") (name "Net-(C2-G2)") (class "Default")
      (node (ref "C2") (pin "4") (pinfunction "G2_4") (pintype "passive"))
      (node (ref "RGLA2") (pin "2") (pinfunction "2_2") (pintype "passive"))
      (node (ref "RL17") (pin "2") (pinfunction "2_2") (pintype "passive"))
    )
    (net (code "37") (name "Net-(IC1A--IN)") (class "Default")
      (node (ref "IC1") (pin "2") (pinfunction "-IN_2") (pintype "input"))
      (node (ref "J1") (pin "2") (pinfunction "2_2") (pintype "passive"))
      (node (ref "RF1") (pin "1") (pinfunction "1_1") (pintype "passive"))
    )
    (net (code "38") (name "Net-(IC1B--IN)") (class "Default")
      (node (ref "IC1") (pin "6") (pinfunction "-IN_6") (pintype "input"))
      (node (ref "J2") (pin "2") (pinfunction "2_2") (pintype "passive"))
      (node (ref "RF2") (pin "2") (pinfunction "2_2") (pintype "passive"))
    )
    (net (code "39") (name "Net-(ICDRIVER-BRAKEN)") (class "Default")
      (node (ref "ICDRIVER") (pin "25") (pinfunction "BRAKEN_25") (pintype "bidirectional"))
      (node (ref "RL7") (pin "2") (pinfunction "2_2") (pintype "passive"))
    )
    (net (code "40") (name "Net-(ICDRIVER-CA)") (class "Default")
      (node (ref "CBOOTC") (pin "2") (pinfunction "2_2") (pintype "passive"))
      (node (ref "ICDRIVER") (pin "13") (pinfunction "CA_13") (pintype "output"))
    )
    (net (code "41") (name "Net-(ICDRIVER-CB)") (class "Default")
      (node (ref "CBOOTB") (pin "2") (pinfunction "2_2") (pintype "passive"))
      (node (ref "ICDRIVER") (pin "9") (pinfunction "CB_9") (pintype "output"))
    )
    (net (code "42") (name "Net-(ICDRIVER-CC)") (class "Default")
      (node (ref "CBOOTA") (pin "1") (pinfunction "1_1") (pintype "passive"))
      (node (ref "ICDRIVER") (pin "5") (pinfunction "CC_5") (pintype "output"))
    )
    (net (code "43") (name "Net-(ICDRIVER-CP1)") (class "Default")
      (node (ref "CPR") (pin "2") (pinfunction "2_2") (pintype "passive"))
      (node (ref "ICDRIVER") (pin "16") (pinfunction "CP1_16") (pintype "input"))
    )
    (net (code "44") (name "Net-(ICDRIVER-CP2)") (class "Default")
      (node (ref "CPR") (pin "1") (pinfunction "1_1") (pintype "passive"))
      (node (ref "ICDRIVER") (pin "15") (pinfunction "CP2_15") (pintype "passive"))
    )
    (net (code "45") (name "Net-(ICDRIVER-DIR)") (class "Default")
      (node (ref "ICDRIVER") (pin "24") (pinfunction "DIR_24") (pintype "input"))
      (node (ref "RL8") (pin "2") (pinfunction "2_2") (pintype "passive"))
    )
    (net (code "46") (name "Net-(ICDRIVER-ENABLE)") (class "Default")
      (node (ref "ICDRIVER") (pin "23") (pinfunction "ENABLE_23") (pintype "input"))
      (node (ref "RL9") (pin "2") (pinfunction "2_2") (pintype "passive"))
    )
    (net (code "47") (name "Net-(ICDRIVER-FAULT)") (class "Default")
      (node (ref "ICDRIVER") (pin "22") (pinfunction "FAULT_22") (pintype "output"))
      (node (ref "RL11") (pin "2") (pinfunction "2_2") (pintype "passive"))
    )
    (net (code "48") (name "Net-(ICDRIVER-GHA)") (class "Default")
      (node (ref "ICDRIVER") (pin "11") (pinfunction "GHA_11") (pintype "output"))
      (node (ref "RGHA") (pin "1") (pinfunction "1_1") (pintype "passive"))
    )
    (net (code "49") (name "Net-(ICDRIVER-GHB)") (class "Default")
      (node (ref "ICDRIVER") (pin "7") (pinfunction "GHB_7") (pintype "output"))
      (node (ref "RGHA2") (pin "1") (pinfunction "1_1") (pintype "passive"))
    )
    (net (code "50") (name "Net-(ICDRIVER-GHC)") (class "Default")
      (node (ref "ICDRIVER") (pin "3") (pinfunction "GHC_3") (pintype "output"))
      (node (ref "RGHA3") (pin "1") (pinfunction "1_1") (pintype "passive"))
    )
    (net (code "51") (name "Net-(ICDRIVER-GLA)") (class "Default")
      (node (ref "ICDRIVER") (pin "10") (pinfunction "GLA_10") (pintype "output"))
      (node (ref "RGLA") (pin "1") (pinfunction "1_1") (pintype "passive"))
    )
    (net (code "52") (name "Net-(ICDRIVER-GLB)") (class "Default")
      (node (ref "ICDRIVER") (pin "6") (pinfunction "GLB_6") (pintype "output"))
      (node (ref "RGLA5") (pin "1") (pinfunction "1_1") (pintype "passive"))
    )
    (net (code "53") (name "Net-(ICDRIVER-GLC)") (class "Default")
      (node (ref "ICDRIVER") (pin "2") (pinfunction "GLC_2") (pintype "output"))
      (node (ref "RGLA7") (pin "1") (pinfunction "1_1") (pintype "passive"))
    )
    (net (code "54") (name "Net-(ICDRIVER-SPEED)") (class "Default")
      (node (ref "ICDRIVER") (pin "19") (pinfunction "SPEED_19") (pintype "input"))
      (node (ref "RL10") (pin "2") (pinfunction "2_2") (pintype "passive"))
    )
    (net (code "55") (name "Net-(ICDRIVER-TDEAD)") (class "Default")
      (node (ref "ICDRIVER") (pin "20") (pinfunction "TDEAD_20") (pintype "input"))
      (node (ref "RDEAD") (pin "2") (pinfunction "2_2") (pintype "passive"))
    )
    (net (code "56") (name "Net-(ICDRIVER-VREG)") (class "Default")
      (node (ref "CREG") (pin "1") (pinfunction "1_1") (pintype "passive"))
      (node (ref "ICDRIVER") (pin "14") (pinfunction "VREG_14") (pintype "power_in"))
    )
    (net (code "57") (name "Net-(ICDRIVER2-BRAKEN)") (class "Default")
      (node (ref "ICDRIVER2") (pin "25") (pinfunction "BRAKEN_25") (pintype "bidirectional"))
      (node (ref "RL18") (pin "2") (pinfunction "2_2") (pintype "passive"))
    )
    (net (code "58") (name "Net-(ICDRIVER2-CA)") (class "Default")
      (node (ref "CBOOTC1") (pin "2") (pinfunction "2_2") (pintype "passive"))
      (node (ref "ICDRIVER2") (pin "13") (pinfunction "CA_13") (pintype "output"))
    )
    (net (code "59") (name "Net-(ICDRIVER2-CB)") (class "Default")
      (node (ref "CBOOTB1") (pin "2") (pinfunction "2_2") (pintype "passive"))
      (node (ref "ICDRIVER2") (pin "9") (pinfunction "CB_9") (pintype "output"))
    )
    (net (code "60") (name "Net-(ICDRIVER2-CC)") (class "Default")
      (node (ref "CBOOTA1") (pin "1") (pinfunction "1_1") (pintype "passive"))
      (node (ref "ICDRIVER2") (pin "5") (pinfunction "CC_5") (pintype "output"))
    )
    (net (code "61") (name "Net-(ICDRIVER2-CP1)") (class "Default")
      (node (ref "CPR1") (pin "2") (pinfunction "2_2") (pintype "passive"))
      (node (ref "ICDRIVER2") (pin "16") (pinfunction "CP1_16") (pintype "input"))
    )
    (net (code "62") (name "Net-(ICDRIVER2-CP2)") (class "Default")
      (node (ref "CPR1") (pin "1") (pinfunction "1_1") (pintype "passive"))
      (node (ref "ICDRIVER2") (pin "15") (pinfunction "CP2_15") (pintype "passive"))
    )
    (net (code "63") (name "Net-(ICDRIVER2-DIR)") (class "Default")
      (node (ref "ICDRIVER2") (pin "24") (pinfunction "DIR_24") (pintype "input"))
      (node (ref "RL19") (pin "2") (pinfunction "2_2") (pintype "passive"))
    )
    (net (code "64") (name "Net-(ICDRIVER2-ENABLE)") (class "Default")
      (node (ref "ICDRIVER2") (pin "23") (pinfunction "ENABLE_23") (pintype "input"))
      (node (ref "RL20") (pin "2") (pinfunction "2_2") (pintype "passive"))
    )
    (net (code "65") (name "Net-(ICDRIVER2-FAULT)") (class "Default")
      (node (ref "ICDRIVER2") (pin "22") (pinfunction "FAULT_22") (pintype "output"))
      (node (ref "RL22") (pin "2") (pinfunction "2_2") (pintype "passive"))
    )
    (net (code "66") (name "Net-(ICDRIVER2-GHA)") (class "Default")
      (node (ref "ICDRIVER2") (pin "11") (pinfunction "GHA_11") (pintype "output"))
      (node (ref "RGHA1") (pin "1") (pinfunction "1_1") (pintype "passive"))
    )
    (net (code "67") (name "Net-(ICDRIVER2-GHB)") (class "Default")
      (node (ref "ICDRIVER2") (pin "7") (pinfunction "GHB_7") (pintype "output"))
      (node (ref "RGLA8") (pin "1") (pinfunction "1_1") (pintype "passive"))
    )
    (net (code "68") (name "Net-(ICDRIVER2-GHC)") (class "Default")
      (node (ref "ICDRIVER2") (pin "3") (pinfunction "GHC_3") (pintype "output"))
      (node (ref "RGLA2") (pin "1") (pinfunction "1_1") (pintype "passive"))
    )
    (net (code "69") (name "Net-(ICDRIVER2-GLA)") (class "Default")
      (node (ref "ICDRIVER2") (pin "10") (pinfunction "GLA_10") (pintype "output"))
      (node (ref "RGLA1") (pin "1") (pinfunction "1_1") (pintype "passive"))
    )
    (net (code "70") (name "Net-(ICDRIVER2-GLB)") (class "Default")
      (node (ref "ICDRIVER2") (pin "6") (pinfunction "GLB_6") (pintype "output"))
      (node (ref "RGLA3") (pin "1") (pinfunction "1_1") (pintype "passive"))
    )
    (net (code "71") (name "Net-(ICDRIVER2-GLC)") (class "Default")
      (node (ref "ICDRIVER2") (pin "2") (pinfunction "GLC_2") (pintype "output"))
      (node (ref "RGLA9") (pin "1") (pinfunction "1_1") (pintype "passive"))
    )
    (net (code "72") (name "Net-(ICDRIVER2-SPEED)") (class "Default")
      (node (ref "ICDRIVER2") (pin "19") (pinfunction "SPEED_19") (pintype "input"))
      (node (ref "RL21") (pin "2") (pinfunction "2_2") (pintype "passive"))
    )
    (net (code "73") (name "Net-(ICDRIVER2-TDEAD)") (class "Default")
      (node (ref "ICDRIVER2") (pin "20") (pinfunction "TDEAD_20") (pintype "input"))
      (node (ref "RDEAD1") (pin "2") (pinfunction "2_2") (pintype "passive"))
    )
    (net (code "74") (name "Net-(ICDRIVER2-VREG)") (class "Default")
      (node (ref "CREG1") (pin "1") (pinfunction "1_1") (pintype "passive"))
      (node (ref "ICDRIVER2") (pin "14") (pinfunction "VREG_14") (pintype "power_in"))
    )
    (net (code "75") (name "Net-(LED1-PadC)") (class "Default")
      (node (ref "LED1") (pin "C") (pinfunction "C_C") (pintype "passive"))
      (node (ref "RL22") (pin "1") (pinfunction "1_1") (pintype "passive"))
    )
    (net (code "76") (name "Net-(LED2-PadC)") (class "Default")
      (node (ref "LED2") (pin "C") (pinfunction "C_C") (pintype "passive"))
      (node (ref "RF11") (pin "1") (pinfunction "1_1") (pintype "passive"))
    )
    (net (code "77") (name "Net-(LED3-PadC)") (class "Default")
      (node (ref "LED3") (pin "C") (pinfunction "C_C") (pintype "passive"))
      (node (ref "RL11") (pin "1") (pinfunction "1_1") (pintype "passive"))
    )
    (net (code "78") (name "Net-(LED4-PadC)") (class "Default")
      (node (ref "LED4") (pin "C") (pinfunction "C_C") (pintype "passive"))
      (node (ref "RF12") (pin "1") (pinfunction "1_1") (pintype "passive"))
    )
    (net (code "79") (name "VOUT1") (class "Default")
      (node (ref "IC1") (pin "1") (pinfunction "OUT_1") (pintype "output"))
      (node (ref "RF1") (pin "2") (pinfunction "2_2") (pintype "passive"))
      (node (ref "U$1") (pin "7") (pinfunction "S_7") (pintype "passive"))
    )
    (net (code "80") (name "VOUT2") (class "Default")
      (node (ref "IC1") (pin "7") (pinfunction "OUT_7") (pintype "output"))
      (node (ref "RF2") (pin "1") (pinfunction "1_1") (pintype "passive"))
      (node (ref "U$2") (pin "7") (pinfunction "S_7") (pintype "passive"))
    )
    (net (code "81") (name "VT") (class "Default")
      (node (ref "J1") (pin "1") (pinfunction "1_1") (pintype "passive"))
      (node (ref "J2") (pin "1") (pinfunction "1_1") (pintype "passive"))
      (node (ref "RF3") (pin "2") (pinfunction "2_2") (pintype "passive"))
      (node (ref "RF4") (pin "1") (pinfunction "1_1") (pintype "passive"))
    )
  )
)
